# DustSensorMk1.net
KiCad netlist of a schematic drawn in EAGLE
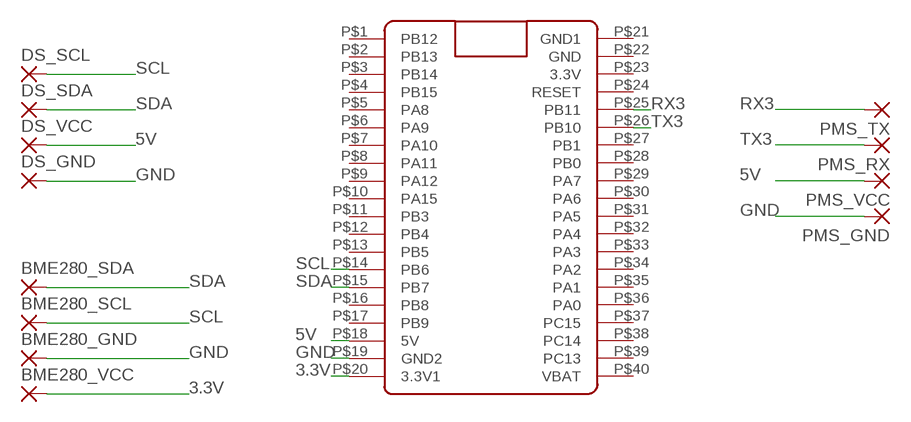
[diagram p0: schematic, sheet 1]

(export (version "E")
  (design (tool "Eeschema 10.0.6"))
  (components
    (comp (ref "BME280_GND")
      (value "2,15/1,0")
      (footprint "eagle-import:2,15_1,0")
      (libsource (lib "eagle-import") (part "2,15/1,0"))
    )
    (comp (ref "BME280_SCL")
      (value "2,15/1,0")
      (footprint "eagle-import:2,15_1,0")
      (libsource (lib "eagle-import") (part "2,15/1,0"))
    )
    (comp (ref "BME280_SDA")
      (value "2,15/1,0")
      (footprint "eagle-import:2,15_1,0")
      (libsource (lib "eagle-import") (part "2,15/1,0"))
    )
    (comp (ref "BME280_VCC")
      (value "2,15/1,0")
      (footprint "eagle-import:2,15_1,0")
      (libsource (lib "eagle-import") (part "2,15/1,0"))
    )
    (comp (ref "DS_GND")
      (value "2,15/1,0")
      (footprint "eagle-import:2,15_1,0")
      (libsource (lib "eagle-import") (part "2,15/1,0"))
    )
    (comp (ref "DS_SCL")
      (value "2,15/1,0")
      (footprint "eagle-import:2,15_1,0")
      (libsource (lib "eagle-import") (part "2,15/1,0"))
    )
    (comp (ref "DS_SDA")
      (value "2,15/1,0")
      (footprint "eagle-import:2,15_1,0")
      (libsource (lib "eagle-import") (part "2,15/1,0"))
    )
    (comp (ref "DS_VCC")
      (value "2,15/1,0")
      (footprint "eagle-import:2,15_1,0")
      (libsource (lib "eagle-import") (part "2,15/1,0"))
    )
    (comp (ref "PMS_GND")
      (value "2,15/1,0")
      (footprint "eagle-import:2,15_1,0")
      (libsource (lib "eagle-import") (part "2,15/1,0"))
    )
    (comp (ref "PMS_RX")
      (value "2,15/1,0")
      (footprint "eagle-import:2,15_1,0")
      (libsource (lib "eagle-import") (part "2,15/1,0"))
    )
    (comp (ref "PMS_TX")
      (value "2,15/1,0")
      (footprint "eagle-import:2,15_1,0")
      (libsource (lib "eagle-import") (part "2,15/1,0"))
    )
    (comp (ref "PMS_VCC")
      (value "2,15/1,0")
      (footprint "eagle-import:2,15_1,0")
      (libsource (lib "eagle-import") (part "2,15/1,0"))
    )
    (comp (ref "U$1")
      (value "BLUE_PILL")
      (footprint "eagle-import:BLUE_PILL")
      (libsource (lib "eagle-import") (part "BLUE_PILL"))
    )
  )
  (nets
    (net (code "1") (name "/3.3V") (class "Default")
      (node (ref "BME280_VCC") (pin "1") (pinfunction "P_1") (pintype "passive"))
      (node (ref "U$1") (pin "P$20") (pinfunction "3.3V1_P$20") (pintype "bidirectional"))
    )
    (net (code "2") (name "/5V") (class "Default")
      (node (ref "DS_VCC") (pin "1") (pinfunction "P_1") (pintype "passive"))
      (node (ref "PMS_VCC") (pin "1") (pinfunction "P_1") (pintype "passive"))
      (node (ref "U$1") (pin "P$18") (pinfunction "5V_P$18") (pintype "bidirectional"))
    )
    (net (code "3") (name "/GND") (class "Default")
      (node (ref "BME280_GND") (pin "1") (pinfunction "P_1") (pintype "passive"))
      (node (ref "DS_GND") (pin "1") (pinfunction "P_1") (pintype "passive"))
      (node (ref "PMS_GND") (pin "1") (pinfunction "P_1") (pintype "passive"))
      (node (ref "U$1") (pin "P$19") (pinfunction "GND2_P$19") (pintype "bidirectional"))
    )
    (net (code "4") (name "/GND1") (class "Default")
      (node (ref "U$1") (pin "P$21") (pinfunction "GND1_P$21") (pintype "power_in"))
    )
    (net (code "5") (name "/RX3") (class "Default")
      (node (ref "PMS_TX") (pin "1") (pinfunction "P_1") (pintype "passive"))
      (node (ref "U$1") (pin "P$25") (pinfunction "PB11_P$25") (pintype "bidirectional"))
    )
    (net (code "6") (name "/SCL") (class "Default")
      (node (ref "BME280_SCL") (pin "1") (pinfunction "P_1") (pintype "passive"))
      (node (ref "DS_SCL") (pin "1") (pinfunction "P_1") (pintype "passive"))
      (node (ref "U$1") (pin "P$14") (pinfunction "PB6_P$14") (pintype "bidirectional"))
    )
    (net (code "7") (name "/SDA") (class "Default")
      (node (ref "BME280_SDA") (pin "1") (pinfunction "P_1") (pintype "passive"))
      (node (ref "DS_SDA") (pin "1") (pinfunction "P_1") (pintype "passive"))
      (node (ref "U$1") (pin "P$15") (pinfunction "PB7_P$15") (pintype "bidirectional"))
    )
    (net (code "8") (name "/TX3") (class "Default")
      (node (ref "PMS_RX") (pin "1") (pinfunction "P_1") (pintype "passive"))
      (node (ref "U$1") (pin "P$26") (pinfunction "PB10_P$26") (pintype "bidirectional"))
    )
    (net (code "9") (name "unconnected-(U$1-3.3V-PadP$23)") (class "Default")
      (node (ref "U$1") (pin "P$23") (pinfunction "3.3V_P$23") (pintype "bidirectional"))
    )
    (net (code "10") (name "unconnected-(U$1-GND-PadP$22)") (class "Default")
      (node (ref "U$1") (pin "P$22") (pinfunction "GND_P$22") (pintype "bidirectional"))
    )
    (net (code "11") (name "unconnected-(U$1-PA0-PadP$36)") (class "Default")
      (node (ref "U$1") (pin "P$36") (pinfunction "PA0_P$36") (pintype "bidirectional"))
    )
    (net (code "12") (name "unconnected-(U$1-PA1-PadP$35)") (class "Default")
      (node (ref "U$1") (pin "P$35") (pinfunction "PA1_P$35") (pintype "bidirectional"))
    )
    (net (code "13") (name "unconnected-(U$1-PA2-PadP$34)") (class "Default")
      (node (ref "U$1") (pin "P$34") (pinfunction "PA2_P$34") (pintype "bidirectional"))
    )
    (net (code "14") (name "unconnected-(U$1-PA3-PadP$33)") (class "Default")
      (node (ref "U$1") (pin "P$33") (pinfunction "PA3_P$33") (pintype "bidirectional"))
    )
    (net (code "15") (name "unconnected-(U$1-PA4-PadP$32)") (class "Default")
      (node (ref "U$1") (pin "P$32") (pinfunction "PA4_P$32") (pintype "bidirectional"))
    )
    (net (code "16") (name "unconnected-(U$1-PA5-PadP$31)") (class "Default")
      (node (ref "U$1") (pin "P$31") (pinfunction "PA5_P$31") (pintype "bidirectional"))
    )
    (net (code "17") (name "unconnected-(U$1-PA6-PadP$30)") (class "Default")
      (node (ref "U$1") (pin "P$30") (pinfunction "PA6_P$30") (pintype "bidirectional"))
    )
    (net (code "18") (name "unconnected-(U$1-PA7-PadP$29)") (class "Default")
      (node (ref "U$1") (pin "P$29") (pinfunction "PA7_P$29") (pintype "bidirectional"))
    )
    (net (code "19") (name "unconnected-(U$1-PA8-PadP$5)") (class "Default")
      (node (ref "U$1") (pin "P$5") (pinfunction "PA8_P$5") (pintype "bidirectional"))
    )
    (net (code "20") (name "unconnected-(U$1-PA9-PadP$6)") (class "Default")
      (node (ref "U$1") (pin "P$6") (pinfunction "PA9_P$6") (pintype "bidirectional"))
    )
    (net (code "21") (name "unconnected-(U$1-PA10-PadP$7)") (class "Default")
      (node (ref "U$1") (pin "P$7") (pinfunction "PA10_P$7") (pintype "bidirectional"))
    )
    (net (code "22") (name "unconnected-(U$1-PA11-PadP$8)") (class "Default")
      (node (ref "U$1") (pin "P$8") (pinfunction "PA11_P$8") (pintype "bidirectional"))
    )
    (net (code "23") (name "unconnected-(U$1-PA12-PadP$9)") (class "Default")
      (node (ref "U$1") (pin "P$9") (pinfunction "PA12_P$9") (pintype "bidirectional"))
    )
    (net (code "24") (name "unconnected-(U$1-PA15-PadP$10)") (class "Default")
      (node (ref "U$1") (pin "P$10") (pinfunction "PA15_P$10") (pintype "bidirectional"))
    )
    (net (code "25") (name "unconnected-(U$1-PB0-PadP$28)") (class "Default")
      (node (ref "U$1") (pin "P$28") (pinfunction "PB0_P$28") (pintype "bidirectional"))
    )
    (net (code "26") (name "unconnected-(U$1-PB1-PadP$27)") (class "Default")
      (node (ref "U$1") (pin "P$27") (pinfunction "PB1_P$27") (pintype "bidirectional"))
    )
    (net (code "27") (name "unconnected-(U$1-PB3-PadP$11)") (class "Default")
      (node (ref "U$1") (pin "P$11") (pinfunction "PB3_P$11") (pintype "bidirectional"))
    )
    (net (code "28") (name "unconnected-(U$1-PB4-PadP$12)") (class "Default")
      (node (ref "U$1") (pin "P$12") (pinfunction "PB4_P$12") (pintype "bidirectional"))
    )
    (net (code "29") (name "unconnected-(U$1-PB5-PadP$13)") (class "Default")
      (node (ref "U$1") (pin "P$13") (pinfunction "PB5_P$13") (pintype "bidirectional"))
    )
    (net (code "30") (name "unconnected-(U$1-PB8-PadP$16)") (class "Default")
      (node (ref "U$1") (pin "P$16") (pinfunction "PB8_P$16") (pintype "bidirectional"))
    )
    (net (code "31") (name "unconnected-(U$1-PB9-PadP$17)") (class "Default")
      (node (ref "U$1") (pin "P$17") (pinfunction "PB9_P$17") (pintype "bidirectional"))
    )
    (net (code "32") (name "unconnected-(U$1-PB12-PadP$1)") (class "Default")
      (node (ref "U$1") (pin "P$1") (pinfunction "PB12_P$1") (pintype "bidirectional"))
    )
    (net (code "33") (name "unconnected-(U$1-PB13-PadP$2)") (class "Default")
      (node (ref "U$1") (pin "P$2") (pinfunction "PB13_P$2") (pintype "bidirectional"))
    )
    (net (code "34") (name "unconnected-(U$1-PB14-PadP$3)") (class "Default")
      (node (ref "U$1") (pin "P$3") (pinfunction "PB14_P$3") (pintype "bidirectional"))
    )
    (net (code "35") (name "unconnected-(U$1-PB15-PadP$4)") (class "Default")
      (node (ref "U$1") (pin "P$4") (pinfunction "PB15_P$4") (pintype "bidirectional"))
    )
    (net (code "36") (name "unconnected-(U$1-PC13-PadP$39)") (class "Default")
      (node (ref "U$1") (pin "P$39") (pinfunction "PC13_P$39") (pintype "bidirectional"))
    )
    (net (code "37") (name "unconnected-(U$1-PC14-PadP$38)") (class "Default")
      (node (ref "U$1") (pin "P$38") (pinfunction "PC14_P$38") (pintype "bidirectional"))
    )
    (net (code "38") (name "unconnected-(U$1-PC15-PadP$37)") (class "Default")
      (node (ref "U$1") (pin "P$37") (pinfunction "PC15_P$37") (pintype "bidirectional"))
    )
    (net (code "39") (name "unconnected-(U$1-RESET-PadP$24)") (class "Default")
      (node (ref "U$1") (pin "P$24") (pinfunction "RESET_P$24") (pintype "bidirectional"))
    )
    (net (code "40") (name "unconnected-(U$1-VBAT-PadP$40)") (class "Default")
      (node (ref "U$1") (pin "P$40") (pinfunction "VBAT_P$40") (pintype "bidirectional"))
    )
  )
)
